# main_esp_board.net
KiCad netlist of a schematic drawn in EAGLE
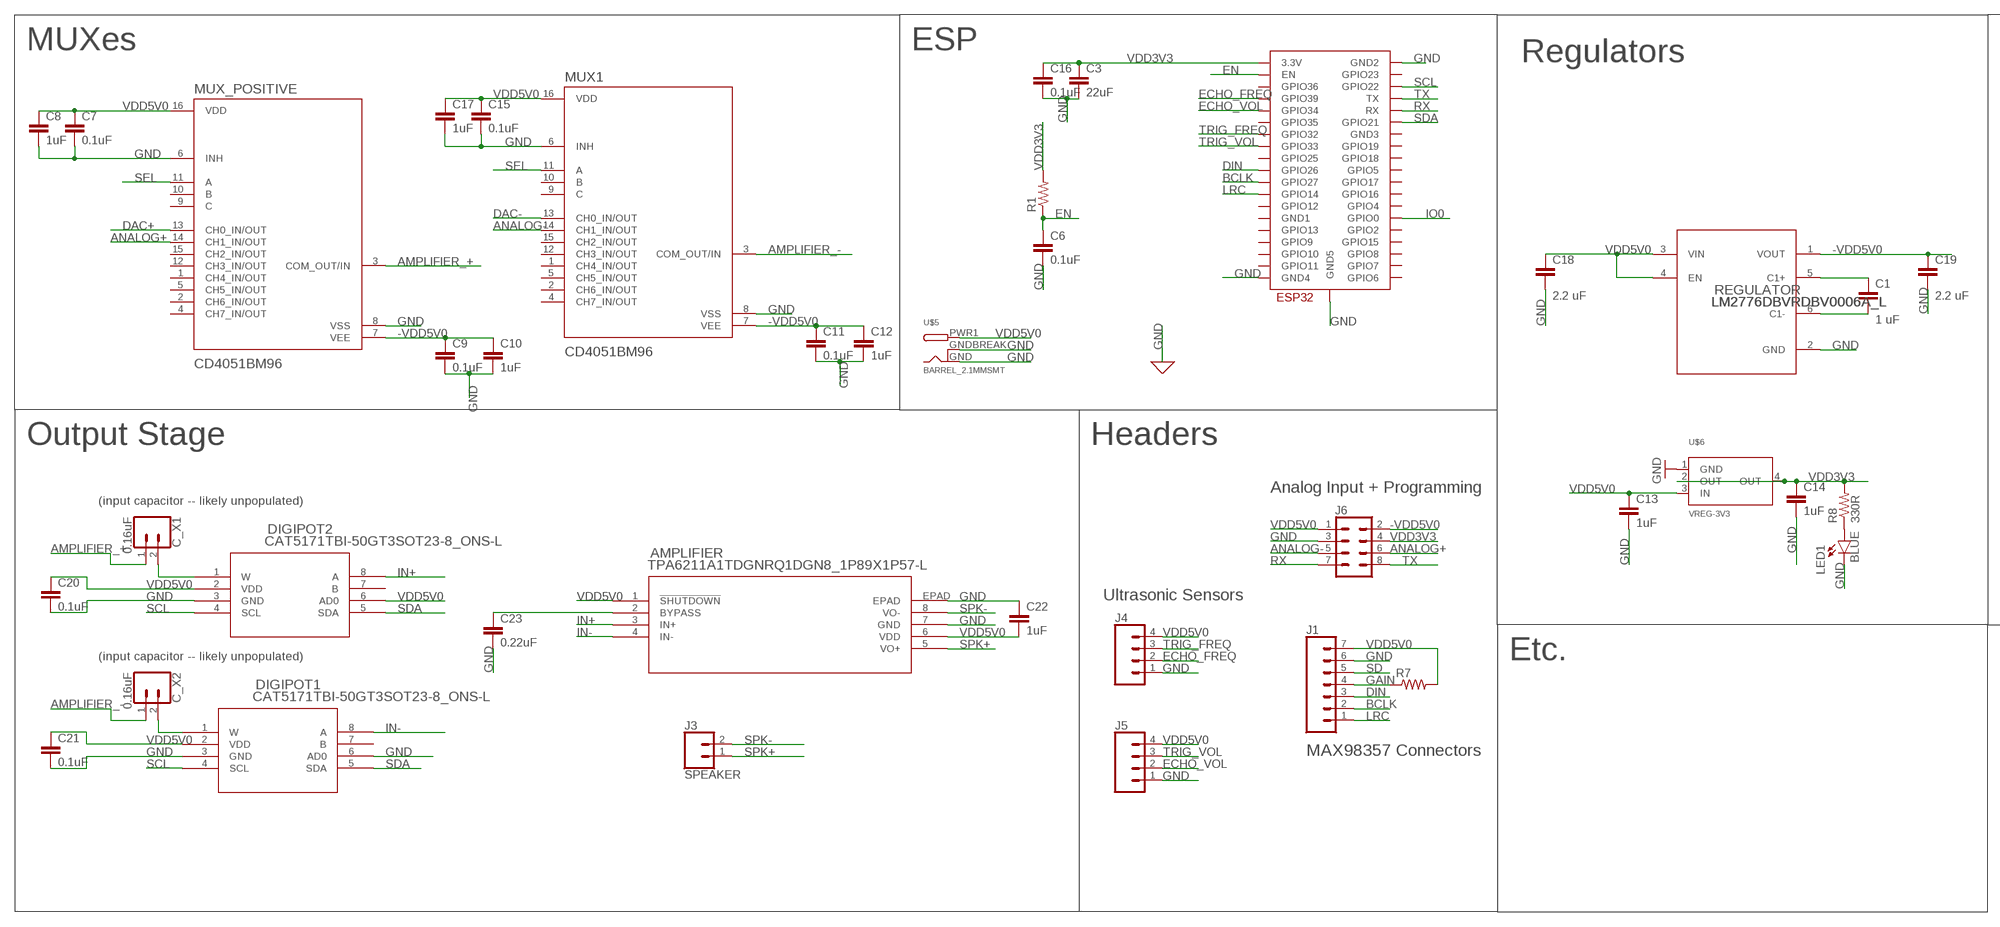
[diagram p0: schematic, sheet 1, part 1 of 2]
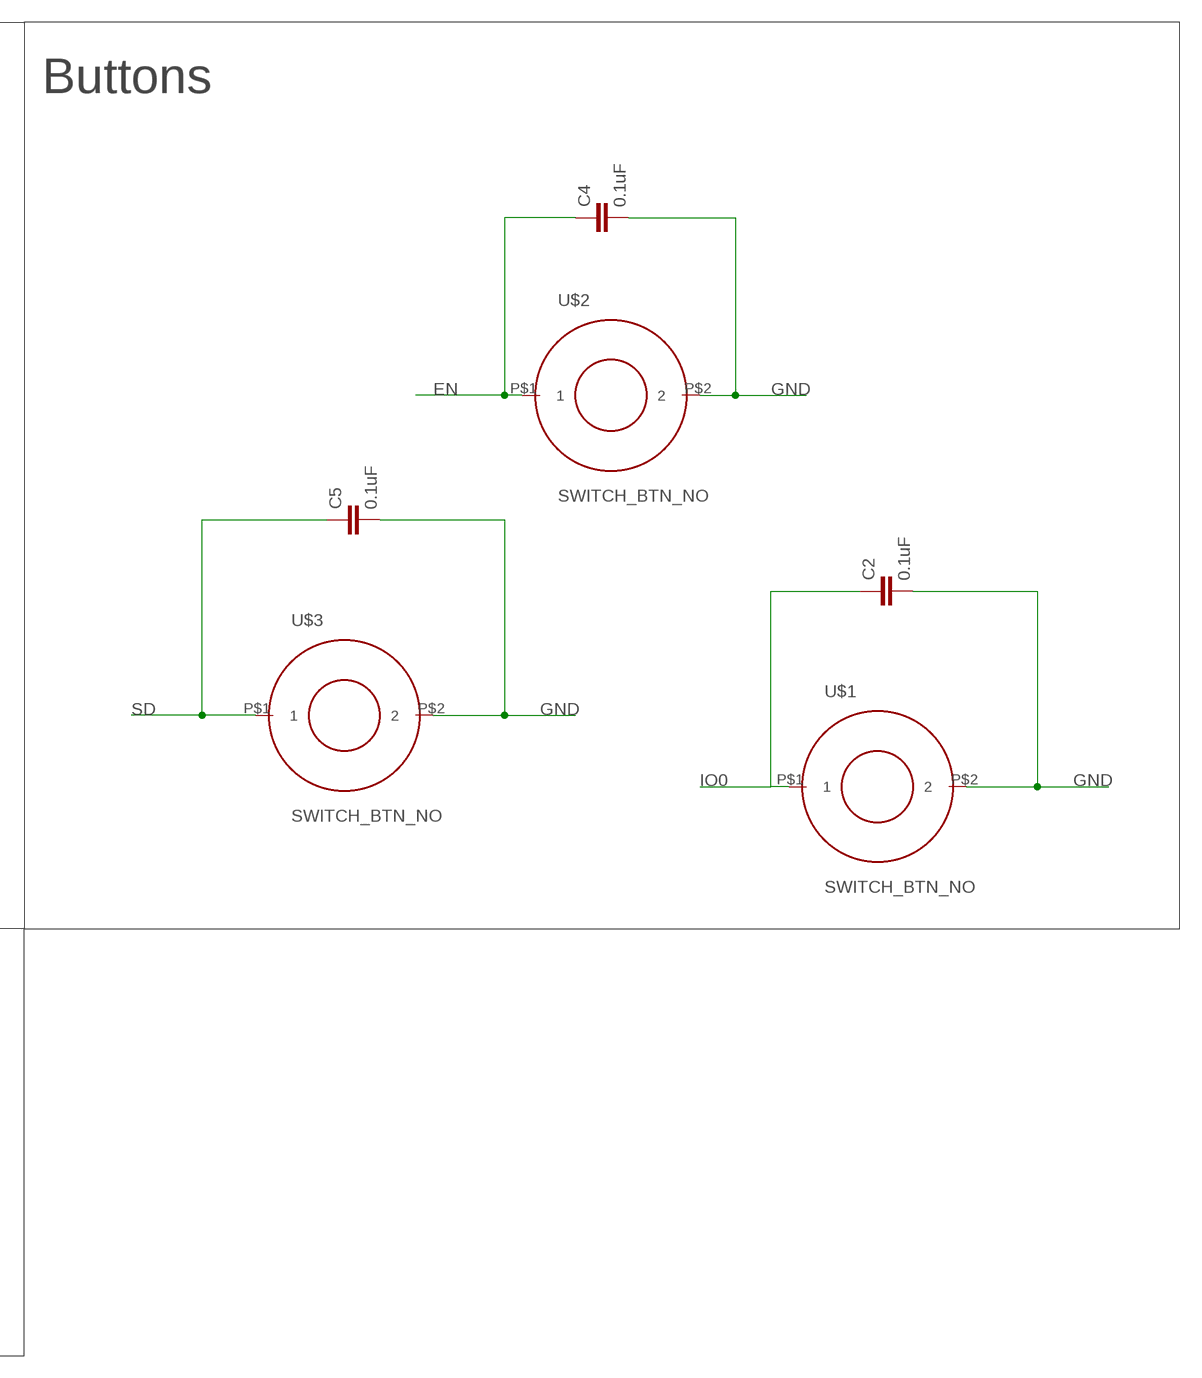
[diagram p1: schematic, sheet 1, part 2 of 2]

(export (version "E")
  (design (tool "Eeschema 10.0.6"))
  (components
    (comp (ref "AMPLIFIER")
      (value "TPA6211A1TDGNRQ1DGN8_1P89X1P57-L")
      (footprint "eagle-import:DGN8_1P89X1P57-L")
      (fields
        (field (name "MANUFACTURER_PART_NUMBER") "TPA6211A1TDGNRQ1")
        (field (name "COPYRIGHT") "Copyright (C) 2025 Ultra Librarian. All rights reserved.")
      )
      (libsource (lib "eagle-import") (part "TPA6211A1TDGNRQ1DGN8_1P89X1P57-L"))
    )
    (comp (ref "C1")
      (value "1 uF")
      (footprint "eagle-import:0805")
      (libsource (lib "eagle-import") (part "CAP"))
    )
    (comp (ref "C2")
      (value "0.1uF")
      (footprint "eagle-import:0805")
      (libsource (lib "eagle-import") (part "CAP"))
    )
    (comp (ref "C3")
      (value "22uF")
      (footprint "eagle-import:0805")
      (libsource (lib "eagle-import") (part "CAP"))
    )
    (comp (ref "C4")
      (value "0.1uF")
      (footprint "eagle-import:0805")
      (libsource (lib "eagle-import") (part "CAP"))
    )
    (comp (ref "C5")
      (value "0.1uF")
      (footprint "eagle-import:0805")
      (libsource (lib "eagle-import") (part "CAP"))
    )
    (comp (ref "C6")
      (value "0.1uF")
      (footprint "eagle-import:0805")
      (libsource (lib "eagle-import") (part "CAP"))
    )
    (comp (ref "C7")
      (value "0.1uF")
      (footprint "eagle-import:0805")
      (libsource (lib "eagle-import") (part "CAP"))
    )
    (comp (ref "C8")
      (value "1uF")
      (footprint "eagle-import:0805")
      (libsource (lib "eagle-import") (part "CAP"))
    )
    (comp (ref "C9")
      (value "0.1uF")
      (footprint "eagle-import:0805")
      (libsource (lib "eagle-import") (part "CAP"))
    )
    (comp (ref "C10")
      (value "1uF")
      (footprint "eagle-import:0805")
      (libsource (lib "eagle-import") (part "CAP"))
    )
    (comp (ref "C11")
      (value "0.1uF")
      (footprint "eagle-import:0805")
      (libsource (lib "eagle-import") (part "CAP"))
    )
    (comp (ref "C12")
      (value "1uF")
      (footprint "eagle-import:0805")
      (libsource (lib "eagle-import") (part "CAP"))
    )
    (comp (ref "C13")
      (value "1uF")
      (footprint "eagle-import:0805")
      (libsource (lib "eagle-import") (part "CAP"))
    )
    (comp (ref "C14")
      (value "1uF")
      (footprint "eagle-import:0805")
      (libsource (lib "eagle-import") (part "CAP"))
    )
    (comp (ref "C15")
      (value "0.1uF")
      (footprint "eagle-import:0805")
      (libsource (lib "eagle-import") (part "CAP"))
    )
    (comp (ref "C16")
      (value "0.1uF")
      (footprint "eagle-import:0805")
      (libsource (lib "eagle-import") (part "CAP"))
    )
    (comp (ref "C17")
      (value "1uF")
      (footprint "eagle-import:0805")
      (libsource (lib "eagle-import") (part "CAP"))
    )
    (comp (ref "C18")
      (value "2.2 uF")
      (footprint "eagle-import:0805")
      (libsource (lib "eagle-import") (part "CAP"))
    )
    (comp (ref "C19")
      (value "2.2 uF")
      (footprint "eagle-import:0805")
      (libsource (lib "eagle-import") (part "CAP"))
    )
    (comp (ref "C20")
      (value "0.1uF")
      (footprint "eagle-import:0805")
      (libsource (lib "eagle-import") (part "CAP"))
    )
    (comp (ref "C21")
      (value "0.1uF")
      (footprint "eagle-import:0805")
      (libsource (lib "eagle-import") (part "CAP"))
    )
    (comp (ref "C22")
      (value "1uF")
      (footprint "eagle-import:0805")
      (libsource (lib "eagle-import") (part "CAP"))
    )
    (comp (ref "C23")
      (value "0.22uF")
      (footprint "eagle-import:0805")
      (libsource (lib "eagle-import") (part "CAP"))
    )
    (comp (ref "C_X1")
      (value "0.16uF")
      (footprint "eagle-import:1X02")
      (libsource (lib "eagle-import") (part "CONN_02"))
    )
    (comp (ref "C_X2")
      (value "0.16uF")
      (footprint "eagle-import:1X02")
      (libsource (lib "eagle-import") (part "CONN_02"))
    )
    (comp (ref "DIGIPOT1")
      (value "CAT5171TBI-50GT3SOT23-8_ONS-L")
      (footprint "eagle-import:SOT23-8_ONS-L")
      (fields
        (field (name "MANUFACTURER_PART_NUMBER") "CAT5171TBI-50GT3")
        (field (name "COPYRIGHT") "Copyright (C) 2025 Ultra Librarian. All rights reserved.")
      )
      (libsource (lib "eagle-import") (part "CAT5171TBI-50GT3SOT23-8_ONS-L"))
    )
    (comp (ref "DIGIPOT2")
      (value "CAT5171TBI-50GT3SOT23-8_ONS-L")
      (footprint "eagle-import:SOT23-8_ONS-L")
      (fields
        (field (name "MANUFACTURER_PART_NUMBER") "CAT5171TBI-50GT3")
        (field (name "COPYRIGHT") "Copyright (C) 2025 Ultra Librarian. All rights reserved.")
      )
      (libsource (lib "eagle-import") (part "CAT5171TBI-50GT3SOT23-8_ONS-L"))
    )
    (comp (ref "ESP32")
      (value "ESP32-WROOM")
      (footprint "eagle-import:ESP32-WROOM")
      (libsource (lib "eagle-import") (part "ESP32-WROOM"))
    )
    (comp (ref "J1")
      (value "CONN_07")
      (footprint "eagle-import:1X07")
      (libsource (lib "eagle-import") (part "CONN_07"))
    )
    (comp (ref "J3")
      (value "SPEAKER")
      (footprint "eagle-import:1X02")
      (libsource (lib "eagle-import") (part "CONN_02"))
    )
    (comp (ref "J4")
      (value "CONN_04PTH")
      (footprint "eagle-import:1X04")
      (libsource (lib "eagle-import") (part "CONN_04PTH"))
    )
    (comp (ref "J5")
      (value "CONN_04PTH")
      (footprint "eagle-import:1X04")
      (libsource (lib "eagle-import") (part "CONN_04PTH"))
    )
    (comp (ref "J6")
      (value "CONN_04X2")
      (footprint "eagle-import:2X4")
      (libsource (lib "eagle-import") (part "CONN_04X2"))
    )
    (comp (ref "LED1")
      (value "BLUE")
      (footprint "eagle-import:LED-0603")
      (libsource (lib "eagle-import") (part "LED0603"))
    )
    (comp (ref "MUX1")
      (value "CD4051BM96")
      (footprint "eagle-import:SOIC127P600X175-16N")
      (fields (field (name "MANUFACTURER") "Texas Instruments"))
      (libsource (lib "eagle-import") (part "CD4051BM96"))
    )
    (comp (ref "MUX_POSITIVE")
      (value "CD4051BM96")
      (footprint "eagle-import:SOIC127P600X175-16N")
      (fields (field (name "MANUFACTURER") "Texas Instruments"))
      (libsource (lib "eagle-import") (part "CD4051BM96"))
    )
    (comp (ref "R1")
      (value "R-US_0207/10")
      (footprint "eagle-import:0207_10")
      (libsource (lib "eagle-import") (part "R-US_0207/10"))
    )
    (comp (ref "R7")
      (value "R-US_0207/10")
      (footprint "eagle-import:0207_10")
      (libsource (lib "eagle-import") (part "R-US_0207/10"))
    )
    (comp (ref "R8")
      (value "330R")
      (footprint "eagle-import:0805")
      (libsource (lib "eagle-import") (part "RES"))
    )
    (comp (ref "REGULATOR")
      (value "LM2776DBVRDBV0006A_L")
      (footprint "eagle-import:DBV0006A_L")
      (fields
        (field (name "MANUFACTURER_PART_NUMBER") "LM2776DBVR")
        (field (name "COPYRIGHT") "Copyright (C) 2025 Ultra Librarian. All rights reserved.")
      )
      (libsource (lib "eagle-import") (part "LM2776DBVRDBV0006A_L"))
    )
    (comp (ref "U$1")
      (value "SWITCH_BTN_NO")
      (footprint "eagle-import:BTN_2")
      (libsource (lib "eagle-import") (part "SWITCH_BTN_NO"))
    )
    (comp (ref "U$2")
      (value "SWITCH_BTN_NO")
      (footprint "eagle-import:BTN_2")
      (libsource (lib "eagle-import") (part "SWITCH_BTN_NO"))
    )
    (comp (ref "U$3")
      (value "SWITCH_BTN_NO")
      (footprint "eagle-import:BTN_2")
      (libsource (lib "eagle-import") (part "SWITCH_BTN_NO"))
    )
    (comp (ref "U$5")
      (value "BARREL_2.1MMSMT")
      (footprint "eagle-import:DCJACK_2MM_SMT")
      (libsource (lib "eagle-import") (part "BARREL_2.1MMSMT"))
    )
    (comp (ref "U$6")
      (value "VREG-3V3")
      (footprint "eagle-import:R-PDSO-G4_TI")
      (libsource (lib "eagle-import") (part "VREG-3V3"))
    )
  )
  (nets
    (net (code "1") (name "/-VDD5V0") (class "Default")
      (node (ref "C10") (pin "1") (pinfunction "1_1") (pintype "passive"))
      (node (ref "C11") (pin "1") (pinfunction "1_1") (pintype "passive"))
      (node (ref "C12") (pin "1") (pinfunction "1_1") (pintype "passive"))
      (node (ref "C19") (pin "1") (pinfunction "1_1") (pintype "passive"))
      (node (ref "C9") (pin "1") (pinfunction "1_1") (pintype "passive"))
      (node (ref "J6") (pin "2") (pinfunction "2_2") (pintype "passive"))
      (node (ref "MUX1") (pin "7") (pinfunction "VEE_7") (pintype "power_in"))
      (node (ref "MUX_POSITIVE") (pin "7") (pinfunction "VEE_7") (pintype "power_in"))
      (node (ref "REGULATOR") (pin "1") (pinfunction "VOUT_1") (pintype "power_in"))
    )
    (net (code "2") (name "/AMPLIFIER_+") (class "Default")
      (node (ref "C_X1") (pin "1") (pinfunction "1_1") (pintype "passive"))
      (node (ref "MUX_POSITIVE") (pin "3") (pinfunction "COM_OUT/IN_3") (pintype "bidirectional"))
    )
    (net (code "3") (name "/AMPLIFIER_-") (class "Default")
      (node (ref "C_X2") (pin "1") (pinfunction "1_1") (pintype "passive"))
      (node (ref "MUX1") (pin "3") (pinfunction "COM_OUT/IN_3") (pintype "bidirectional"))
    )
    (net (code "4") (name "/ANALOG+") (class "Default")
      (node (ref "J6") (pin "6") (pinfunction "6_6") (pintype "passive"))
      (node (ref "MUX_POSITIVE") (pin "14") (pinfunction "CH1_IN/OUT_14") (pintype "bidirectional"))
    )
    (net (code "5") (name "/ANALOG-") (class "Default")
      (node (ref "J6") (pin "5") (pinfunction "5_5") (pintype "passive"))
      (node (ref "MUX1") (pin "14") (pinfunction "CH1_IN/OUT_14") (pintype "bidirectional"))
    )
    (net (code "6") (name "/BCLK") (class "Default")
      (node (ref "ESP32") (pin "IO27") (pinfunction "GPIO27_IO27") (pintype "bidirectional"))
      (node (ref "J1") (pin "2") (pinfunction "2_2") (pintype "passive"))
    )
    (net (code "7") (name "/DAC+") (class "Default")
      (node (ref "MUX_POSITIVE") (pin "13") (pinfunction "CH0_IN/OUT_13") (pintype "bidirectional"))
    )
    (net (code "8") (name "/DAC-") (class "Default")
      (node (ref "MUX1") (pin "13") (pinfunction "CH0_IN/OUT_13") (pintype "bidirectional"))
    )
    (net (code "9") (name "/DIN") (class "Default")
      (node (ref "ESP32") (pin "IO26") (pinfunction "GPIO26_IO26") (pintype "bidirectional"))
      (node (ref "J1") (pin "3") (pinfunction "3_3") (pintype "passive"))
    )
    (net (code "10") (name "/ECHO_FREQ") (class "Default")
      (node (ref "ESP32") (pin "SENSOR_VN") (pinfunction "GPIO39_SENSOR_VN") (pintype "bidirectional"))
      (node (ref "J4") (pin "2") (pinfunction "2_2") (pintype "passive"))
    )
    (net (code "11") (name "/ECHO_VOL") (class "Default")
      (node (ref "ESP32") (pin "IO34") (pinfunction "GPIO34_IO34") (pintype "bidirectional"))
      (node (ref "J5") (pin "2") (pinfunction "2_2") (pintype "passive"))
    )
    (net (code "12") (name "/EN") (class "Default")
      (node (ref "C4") (pin "1") (pinfunction "1_1") (pintype "passive"))
      (node (ref "C6") (pin "1") (pinfunction "1_1") (pintype "passive"))
      (node (ref "ESP32") (pin "EN") (pinfunction "EN_EN") (pintype "bidirectional"))
      (node (ref "R1") (pin "1") (pinfunction "1_1") (pintype "passive"))
      (node (ref "U$2") (pin "P$1") (pinfunction "1_P$1") (pintype "bidirectional"))
    )
    (net (code "13") (name "/GAIN") (class "Default")
      (node (ref "J1") (pin "4") (pinfunction "4_4") (pintype "passive"))
      (node (ref "R7") (pin "1") (pinfunction "1_1") (pintype "passive"))
    )
    (net (code "14") (name "/IN+") (class "Default")
      (node (ref "AMPLIFIER") (pin "3") (pinfunction "IN+_3") (pintype "input"))
      (node (ref "DIGIPOT2") (pin "8") (pinfunction "A_8") (pintype "passive"))
    )
    (net (code "15") (name "/IN-") (class "Default")
      (node (ref "AMPLIFIER") (pin "4") (pinfunction "IN-_4") (pintype "input"))
      (node (ref "DIGIPOT1") (pin "8") (pinfunction "A_8") (pintype "passive"))
    )
    (net (code "16") (name "/IO0") (class "Default")
      (node (ref "C2") (pin "1") (pinfunction "1_1") (pintype "passive"))
      (node (ref "ESP32") (pin "IO0") (pinfunction "GPIO0_IO0") (pintype "bidirectional"))
      (node (ref "U$1") (pin "P$1") (pinfunction "1_P$1") (pintype "bidirectional"))
    )
    (net (code "17") (name "/LRC") (class "Default")
      (node (ref "ESP32") (pin "IO14") (pinfunction "GPIO14_IO14") (pintype "bidirectional"))
      (node (ref "J1") (pin "1") (pinfunction "1_1") (pintype "passive"))
    )
    (net (code "18") (name "/RX") (class "Default")
      (node (ref "ESP32") (pin "RX") (pinfunction "RX_RX") (pintype "bidirectional"))
      (node (ref "J6") (pin "7") (pinfunction "7_7") (pintype "passive"))
    )
    (net (code "19") (name "/SCL") (class "Default")
      (node (ref "DIGIPOT1") (pin "4") (pinfunction "SCL_4") (pintype "input"))
      (node (ref "DIGIPOT2") (pin "4") (pinfunction "SCL_4") (pintype "input"))
      (node (ref "ESP32") (pin "IO22") (pinfunction "GPIO22_IO22") (pintype "bidirectional"))
    )
    (net (code "20") (name "/SD") (class "Default")
      (node (ref "C5") (pin "1") (pinfunction "1_1") (pintype "passive"))
      (node (ref "J1") (pin "5") (pinfunction "5_5") (pintype "passive"))
      (node (ref "U$3") (pin "P$1") (pinfunction "1_P$1") (pintype "bidirectional"))
    )
    (net (code "21") (name "/SDA") (class "Default")
      (node (ref "DIGIPOT1") (pin "5") (pinfunction "SDA_5") (pintype "input"))
      (node (ref "DIGIPOT2") (pin "5") (pinfunction "SDA_5") (pintype "input"))
      (node (ref "ESP32") (pin "IO21") (pinfunction "GPIO21_IO21") (pintype "bidirectional"))
    )
    (net (code "22") (name "/SEL") (class "Default")
      (node (ref "MUX1") (pin "11") (pinfunction "A_11") (pintype "input"))
      (node (ref "MUX_POSITIVE") (pin "11") (pinfunction "A_11") (pintype "input"))
    )
    (net (code "23") (name "/SPK+") (class "Default")
      (node (ref "AMPLIFIER") (pin "5") (pinfunction "VO+_5") (pintype "output"))
      (node (ref "J3") (pin "1") (pinfunction "1_1") (pintype "passive"))
    )
    (net (code "24") (name "/SPK-") (class "Default")
      (node (ref "AMPLIFIER") (pin "8") (pinfunction "VO-_8") (pintype "output"))
      (node (ref "J3") (pin "2") (pinfunction "2_2") (pintype "passive"))
    )
    (net (code "25") (name "/TRIG_FREQ") (class "Default")
      (node (ref "ESP32") (pin "IO32") (pinfunction "GPIO32_IO32") (pintype "bidirectional"))
      (node (ref "J4") (pin "3") (pinfunction "3_3") (pintype "passive"))
    )
    (net (code "26") (name "/TRIG_VOL") (class "Default")
      (node (ref "ESP32") (pin "IO33") (pinfunction "GPIO33_IO33") (pintype "bidirectional"))
      (node (ref "J5") (pin "3") (pinfunction "3_3") (pintype "passive"))
    )
    (net (code "27") (name "/TX") (class "Default")
      (node (ref "ESP32") (pin "TX") (pinfunction "TX_TX") (pintype "bidirectional"))
      (node (ref "J6") (pin "8") (pinfunction "8_8") (pintype "passive"))
    )
    (net (code "28") (name "/VDD3V3") (class "Default")
      (node (ref "C14") (pin "1") (pinfunction "1_1") (pintype "passive"))
      (node (ref "C16") (pin "1") (pinfunction "1_1") (pintype "passive"))
      (node (ref "C3") (pin "1") (pinfunction "1_1") (pintype "passive"))
      (node (ref "ESP32") (pin "3V3") (pinfunction "3.3V_3V3") (pintype "bidirectional"))
      (node (ref "J6") (pin "4") (pinfunction "4_4") (pintype "passive"))
      (node (ref "R1") (pin "2") (pinfunction "2_2") (pintype "passive"))
      (node (ref "R8") (pin "2") (pinfunction "2_2") (pintype "passive"))
      (node (ref "U$6") (pin "2") (pinfunction "OUT_2") (pintype "bidirectional"))
      (node (ref "U$6") (pin "4") (pinfunction "OUT_4") (pintype "bidirectional"))
    )
    (net (code "29") (name "/VDD5V0") (class "Default")
      (node (ref "AMPLIFIER") (pin "1") (pinfunction "~{SHUTDOWN}_1") (pintype "input"))
      (node (ref "AMPLIFIER") (pin "6") (pinfunction "VDD_6") (pintype "power_in"))
      (node (ref "C13") (pin "1") (pinfunction "1_1") (pintype "passive"))
      (node (ref "C15") (pin "1") (pinfunction "1_1") (pintype "passive"))
      (node (ref "C17") (pin "1") (pinfunction "1_1") (pintype "passive"))
      (node (ref "C18") (pin "1") (pinfunction "1_1") (pintype "passive"))
      (node (ref "C20") (pin "1") (pinfunction "1_1") (pintype "passive"))
      (node (ref "C21") (pin "1") (pinfunction "1_1") (pintype "passive"))
      (node (ref "C22") (pin "2") (pinfunction "2_2") (pintype "passive"))
      (node (ref "C7") (pin "1") (pinfunction "1_1") (pintype "passive"))
      (node (ref "C8") (pin "1") (pinfunction "1_1") (pintype "passive"))
      (node (ref "DIGIPOT1") (pin "2") (pinfunction "VDD_2") (pintype "power_in"))
      (node (ref "DIGIPOT2") (pin "2") (pinfunction "VDD_2") (pintype "power_in"))
      (node (ref "DIGIPOT2") (pin "6") (pinfunction "AD0_6") (pintype "input"))
      (node (ref "J1") (pin "7") (pinfunction "7_7") (pintype "passive"))
      (node (ref "J4") (pin "4") (pinfunction "4_4") (pintype "passive"))
      (node (ref "J5") (pin "4") (pinfunction "4_4") (pintype "passive"))
      (node (ref "J6") (pin "1") (pinfunction "1_1") (pintype "passive"))
      (node (ref "MUX1") (pin "16") (pinfunction "VDD_16") (pintype "power_in"))
      (node (ref "MUX_POSITIVE") (pin "16") (pinfunction "VDD_16") (pintype "power_in"))
      (node (ref "R7") (pin "2") (pinfunction "2_2") (pintype "passive"))
      (node (ref "REGULATOR") (pin "3") (pinfunction "VIN_3") (pintype "power_in"))
      (node (ref "REGULATOR") (pin "4") (pinfunction "EN_4") (pintype "input"))
      (node (ref "U$5") (pin "PWR1") (pinfunction "PWR_PWR1") (pintype "power_in"))
      (node (ref "U$6") (pin "3") (pinfunction "IN_3") (pintype "bidirectional"))
    )
    (net (code "30") (name "GND") (class "Default")
      (node (ref "AMPLIFIER") (pin "7") (pinfunction "GND_7") (pintype "power_in"))
      (node (ref "AMPLIFIER") (pin "EPAD") (pinfunction "EPAD_EPAD") (pintype "passive"))
      (node (ref "C10") (pin "2") (pinfunction "2_2") (pintype "passive"))
      (node (ref "C11") (pin "2") (pinfunction "2_2") (pintype "passive"))
      (node (ref "C12") (pin "2") (pinfunction "2_2") (pintype "passive"))
      (node (ref "C13") (pin "2") (pinfunction "2_2") (pintype "passive"))
      (node (ref "C14") (pin "2") (pinfunction "2_2") (pintype "passive"))
      (node (ref "C15") (pin "2") (pinfunction "2_2") (pintype "passive"))
      (node (ref "C16") (pin "2") (pinfunction "2_2") (pintype "passive"))
      (node (ref "C17") (pin "2") (pinfunction "2_2") (pintype "passive"))
      (node (ref "C18") (pin "2") (pinfunction "2_2") (pintype "passive"))
      (node (ref "C19") (pin "2") (pinfunction "2_2") (pintype "passive"))
      (node (ref "C2") (pin "2") (pinfunction "2_2") (pintype "passive"))
      (node (ref "C20") (pin "2") (pinfunction "2_2") (pintype "passive"))
      (node (ref "C21") (pin "2") (pinfunction "2_2") (pintype "passive"))
      (node (ref "C22") (pin "1") (pinfunction "1_1") (pintype "passive"))
      (node (ref "C23") (pin "2") (pinfunction "2_2") (pintype "passive"))
      (node (ref "C3") (pin "2") (pinfunction "2_2") (pintype "passive"))
      (node (ref "C4") (pin "2") (pinfunction "2_2") (pintype "passive"))
      (node (ref "C5") (pin "2") (pinfunction "2_2") (pintype "passive"))
      (node (ref "C6") (pin "2") (pinfunction "2_2") (pintype "passive"))
      (node (ref "C7") (pin "2") (pinfunction "2_2") (pintype "passive"))
      (node (ref "C8") (pin "2") (pinfunction "2_2") (pintype "passive"))
      (node (ref "C9") (pin "2") (pinfunction "2_2") (pintype "passive"))
      (node (ref "DIGIPOT1") (pin "3") (pinfunction "GND_3") (pintype "power_in"))
      (node (ref "DIGIPOT1") (pin "6") (pinfunction "AD0_6") (pintype "input"))
      (node (ref "DIGIPOT2") (pin "3") (pinfunction "GND_3") (pintype "power_in"))
      (node (ref "ESP32") (pin "GND2") (pinfunction "GND2_GND2") (pintype "bidirectional"))
      (node (ref "ESP32") (pin "GND4") (pinfunction "GND4_GND4") (pintype "bidirectional"))
      (node (ref "ESP32") (pin "GND5") (pinfunction "GND5_GND5") (pintype "bidirectional"))
      (node (ref "J1") (pin "6") (pinfunction "6_6") (pintype "passive"))
      (node (ref "J4") (pin "1") (pinfunction "1_1") (pintype "passive"))
      (node (ref "J5") (pin "1") (pinfunction "1_1") (pintype "passive"))
      (node (ref "J6") (pin "3") (pinfunction "3_3") (pintype "passive"))
      (node (ref "LED1") (pin "C") (pinfunction "C_C") (pintype "passive"))
      (node (ref "MUX1") (pin "6") (pinfunction "INH_6") (pintype "input"))
      (node (ref "MUX1") (pin "8") (pinfunction "VSS_8") (pintype "power_in"))
      (node (ref "MUX_POSITIVE") (pin "6") (pinfunction "INH_6") (pintype "input"))
      (node (ref "MUX_POSITIVE") (pin "8") (pinfunction "VSS_8") (pintype "power_in"))
      (node (ref "REGULATOR") (pin "2") (pinfunction "GND_2") (pintype "power_in"))
      (node (ref "U$1") (pin "P$2") (pinfunction "2_P$2") (pintype "bidirectional"))
      (node (ref "U$2") (pin "P$2") (pinfunction "2_P$2") (pintype "bidirectional"))
      (node (ref "U$3") (pin "P$2") (pinfunction "2_P$2") (pintype "bidirectional"))
      (node (ref "U$5") (pin "GND") (pinfunction "GND_GND") (pintype "power_in"))
      (node (ref "U$5") (pin "GNDBREAK") (pinfunction "GNDBREAK_GNDBREAK") (pintype "power_in"))
      (node (ref "U$6") (pin "1") (pinfunction "GND_1") (pintype "bidirectional"))
    )
    (net (code "31") (name "Net-(AMPLIFIER-BYPASS)") (class "Default")
      (node (ref "AMPLIFIER") (pin "2") (pinfunction "BYPASS_2") (pintype "passive"))
      (node (ref "C23") (pin "1") (pinfunction "1_1") (pintype "passive"))
    )
    (net (code "32") (name "Net-(DIGIPOT1-W)") (class "Default")
      (node (ref "C_X2") (pin "2") (pinfunction "2_2") (pintype "passive"))
      (node (ref "DIGIPOT1") (pin "1") (pinfunction "W_1") (pintype "passive"))
    )
    (net (code "33") (name "Net-(DIGIPOT2-W)") (class "Default")
      (node (ref "C_X1") (pin "2") (pinfunction "2_2") (pintype "passive"))
      (node (ref "DIGIPOT2") (pin "1") (pinfunction "W_1") (pintype "passive"))
    )
    (net (code "34") (name "Net-(LED1-PadA)") (class "Default")
      (node (ref "LED1") (pin "A") (pinfunction "A_A") (pintype "passive"))
      (node (ref "R8") (pin "1") (pinfunction "1_1") (pintype "passive"))
    )
    (net (code "35") (name "Net-(REGULATOR-C1+)") (class "Default")
      (node (ref "C1") (pin "1") (pinfunction "1_1") (pintype "passive"))
      (node (ref "REGULATOR") (pin "5") (pinfunction "C1+_5") (pintype "passive"))
    )
    (net (code "36") (name "Net-(REGULATOR-C1-)") (class "Default")
      (node (ref "C1") (pin "2") (pinfunction "2_2") (pintype "passive"))
      (node (ref "REGULATOR") (pin "6") (pinfunction "C1-_6") (pintype "passive"))
    )
    (net (code "37") (name "unconnected-(DIGIPOT1-B-Pad7)") (class "Default")
      (node (ref "DIGIPOT1") (pin "7") (pinfunction "B_7") (pintype "passive"))
    )
    (net (code "38") (name "unconnected-(DIGIPOT2-B-Pad7)") (class "Default")
      (node (ref "DIGIPOT2") (pin "7") (pinfunction "B_7") (pintype "passive"))
    )
    (net (code "39") (name "unconnected-(ESP32-GPIO2-PadIO2)") (class "Default")
      (node (ref "ESP32") (pin "IO2") (pinfunction "GPIO2_IO2") (pintype "bidirectional"))
    )
    (net (code "40") (name "unconnected-(ESP32-GPIO4-PadIO4)") (class "Default")
      (node (ref "ESP32") (pin "IO4") (pinfunction "GPIO4_IO4") (pintype "bidirectional"))
    )
    (net (code "41") (name "unconnected-(ESP32-GPIO5-PadIO5)") (class "Default")
      (node (ref "ESP32") (pin "IO5") (pinfunction "GPIO5_IO5") (pintype "bidirectional"))
    )
    (net (code "42") (name "unconnected-(ESP32-GPIO6-PadCLK)") (class "Default")
      (node (ref "ESP32") (pin "CLK") (pinfunction "GPIO6_CLK") (pintype "bidirectional"))
    )
    (net (code "43") (name "unconnected-(ESP32-GPIO7-PadSD0)") (class "Default")
      (node (ref "ESP32") (pin "SD0") (pinfunction "GPIO7_SD0") (pintype "bidirectional"))
    )
    (net (code "44") (name "unconnected-(ESP32-GPIO8-PadSD1)") (class "Default")
      (node (ref "ESP32") (pin "SD1") (pinfunction "GPIO8_SD1") (pintype "bidirectional"))
    )
    (net (code "45") (name "unconnected-(ESP32-GPIO9-PadSD2)") (class "Default")
      (node (ref "ESP32") (pin "SD2") (pinfunction "GPIO9_SD2") (pintype "bidirectional"))
    )
    (net (code "46") (name "unconnected-(ESP32-GPIO10-PadSD3)") (class "Default")
      (node (ref "ESP32") (pin "SD3") (pinfunction "GPIO10_SD3") (pintype "bidirectional"))
    )
    (net (code "47") (name "unconnected-(ESP32-GPIO11-PadCMD)") (class "Default")
      (node (ref "ESP32") (pin "CMD") (pinfunction "GPIO11_CMD") (pintype "bidirectional"))
    )
    (net (code "48") (name "unconnected-(ESP32-GPIO12-PadIO12)") (class "Default")
      (node (ref "ESP32") (pin "IO12") (pinfunction "GPIO12_IO12") (pintype "bidirectional"))
    )
    (net (code "49") (name "unconnected-(ESP32-GPIO13-PadIO13)") (class "Default")
      (node (ref "ESP32") (pin "IO13") (pinfunction "GPIO13_IO13") (pintype "bidirectional"))
    )
    (net (code "50") (name "unconnected-(ESP32-GPIO15-PadIO15)") (class "Default")
      (node (ref "ESP32") (pin "IO15") (pinfunction "GPIO15_IO15") (pintype "bidirectional"))
    )
    (net (code "51") (name "unconnected-(ESP32-GPIO16-PadIO16)") (class "Default")
      (node (ref "ESP32") (pin "IO16") (pinfunction "GPIO16_IO16") (pintype "bidirectional"))
    )
    (net (code "52") (name "unconnected-(ESP32-GPIO17-PadIO17)") (class "Default")
      (node (ref "ESP32") (pin "IO17") (pinfunction "GPIO17_IO17") (pintype "bidirectional"))
    )
    (net (code "53") (name "unconnected-(ESP32-GPIO18-PadIO18)") (class "Default")
      (node (ref "ESP32") (pin "IO18") (pinfunction "GPIO18_IO18") (pintype "bidirectional"))
    )
    (net (code "54") (name "unconnected-(ESP32-GPIO19-PadIO19)") (class "Default")
      (node (ref "ESP32") (pin "IO19") (pinfunction "GPIO19_IO19") (pintype "bidirectional"))
    )
    (net (code "55") (name "unconnected-(ESP32-GPIO23-PadIO23)") (class "Default")
      (node (ref "ESP32") (pin "IO23") (pinfunction "GPIO23_IO23") (pintype "bidirectional"))
    )
    (net (code "56") (name "unconnected-(ESP32-GPIO25-PadIO25)") (class "Default")
      (node (ref "ESP32") (pin "IO25") (pinfunction "GPIO25_IO25") (pintype "bidirectional"))
    )
    (net (code "57") (name "unconnected-(ESP32-GPIO35-PadIO35)") (class "Default")
      (node (ref "ESP32") (pin "IO35") (pinfunction "GPIO35_IO35") (pintype "bidirectional"))
    )
    (net (code "58") (name "unconnected-(ESP32-GPIO36-PadSENSOR_VP)") (class "Default")
      (node (ref "ESP32") (pin "SENSOR_VP") (pinfunction "GPIO36_SENSOR_VP") (pintype "bidirectional"))
    )
    (net (code "59") (name "unconnected-(ESP32-PadGND1)") (class "Default")
      (node (ref "ESP32") (pin "GND1") (pinfunction "GND1_GND1") (pintype "bidirectional"))
    )
    (net (code "60") (name "unconnected-(ESP32-PadGND3)") (class "Default")
      (node (ref "ESP32") (pin "GND3") (pinfunction "GND3_GND3") (pintype "bidirectional"))
    )
    (net (code "61") (name "unconnected-(MUX1-B-Pad10)") (class "Default")
      (node (ref "MUX1") (pin "10") (pinfunction "B_10") (pintype "input"))
    )
    (net (code "62") (name "unconnected-(MUX1-C-Pad9)") (class "Default")
      (node (ref "MUX1") (pin "9") (pinfunction "C_9") (pintype "input"))
    )
    (net (code "63") (name "unconnected-(MUX1-CH2_IN{slash}OUT-Pad15)") (class "Default")
      (node (ref "MUX1") (pin "15") (pinfunction "CH2_IN/OUT_15") (pintype "bidirectional"))
    )
    (net (code "64") (name "unconnected-(MUX1-CH3_IN{slash}OUT-Pad12)") (class "Default")
      (node (ref "MUX1") (pin "12") (pinfunction "CH3_IN/OUT_12") (pintype "bidirectional"))
    )
    (net (code "65") (name "unconnected-(MUX1-CH4_IN{slash}OUT-Pad1)") (class "Default")
      (node (ref "MUX1") (pin "1") (pinfunction "CH4_IN/OUT_1") (pintype "bidirectional"))
    )
    (net (code "66") (name "unconnected-(MUX1-CH5_IN{slash}OUT-Pad5)") (class "Default")
      (node (ref "MUX1") (pin "5") (pinfunction "CH5_IN/OUT_5") (pintype "bidirectional"))
    )
    (net (code "67") (name "unconnected-(MUX1-CH6_IN{slash}OUT-Pad2)") (class "Default")
      (node (ref "MUX1") (pin "2") (pinfunction "CH6_IN/OUT_2") (pintype "bidirectional"))
    )
    (net (code "68") (name "unconnected-(MUX1-CH7_IN{slash}OUT-Pad4)") (class "Default")
      (node (ref "MUX1") (pin "4") (pinfunction "CH7_IN/OUT_4") (pintype "bidirectional"))
    )
    (net (code "69") (name "unconnected-(MUX_POSITIVE-B-Pad10)") (class "Default")
      (node (ref "MUX_POSITIVE") (pin "10") (pinfunction "B_10") (pintype "input"))
    )
    (net (code "70") (name "unconnected-(MUX_POSITIVE-C-Pad9)") (class "Default")
      (node (ref "MUX_POSITIVE") (pin "9") (pinfunction "C_9") (pintype "input"))
    )
    (net (code "71") (name "unconnected-(MUX_POSITIVE-CH2_IN{slash}OUT-Pad15)") (class "Default")
      (node (ref "MUX_POSITIVE") (pin "15") (pinfunction "CH2_IN/OUT_15") (pintype "bidirectional"))
    )
    (net (code "72") (name "unconnected-(MUX_POSITIVE-CH3_IN{slash}OUT-Pad12)") (class "Default")
      (node (ref "MUX_POSITIVE") (pin "12") (pinfunction "CH3_IN/OUT_12") (pintype "bidirectional"))
    )
    (net (code "73") (name "unconnected-(MUX_POSITIVE-CH4_IN{slash}OUT-Pad1)") (class "Default")
      (node (ref "MUX_POSITIVE") (pin "1") (pinfunction "CH4_IN/OUT_1") (pintype "bidirectional"))
    )
    (net (code "74") (name "unconnected-(MUX_POSITIVE-CH5_IN{slash}OUT-Pad5)") (class "Default")
      (node (ref "MUX_POSITIVE") (pin "5") (pinfunction "CH5_IN/OUT_5") (pintype "bidirectional"))
    )
    (net (code "75") (name "unconnected-(MUX_POSITIVE-CH6_IN{slash}OUT-Pad2)") (class "Default")
      (node (ref "MUX_POSITIVE") (pin "2") (pinfunction "CH6_IN/OUT_2") (pintype "bidirectional"))
    )
    (net (code "76") (name "unconnected-(MUX_POSITIVE-CH7_IN{slash}OUT-Pad4)") (class "Default")
      (node (ref "MUX_POSITIVE") (pin "4") (pinfunction "CH7_IN/OUT_4") (pintype "bidirectional"))
    )
  )
)
